# Main.net
KiCad netlist of a schematic drawn in Altium Designer
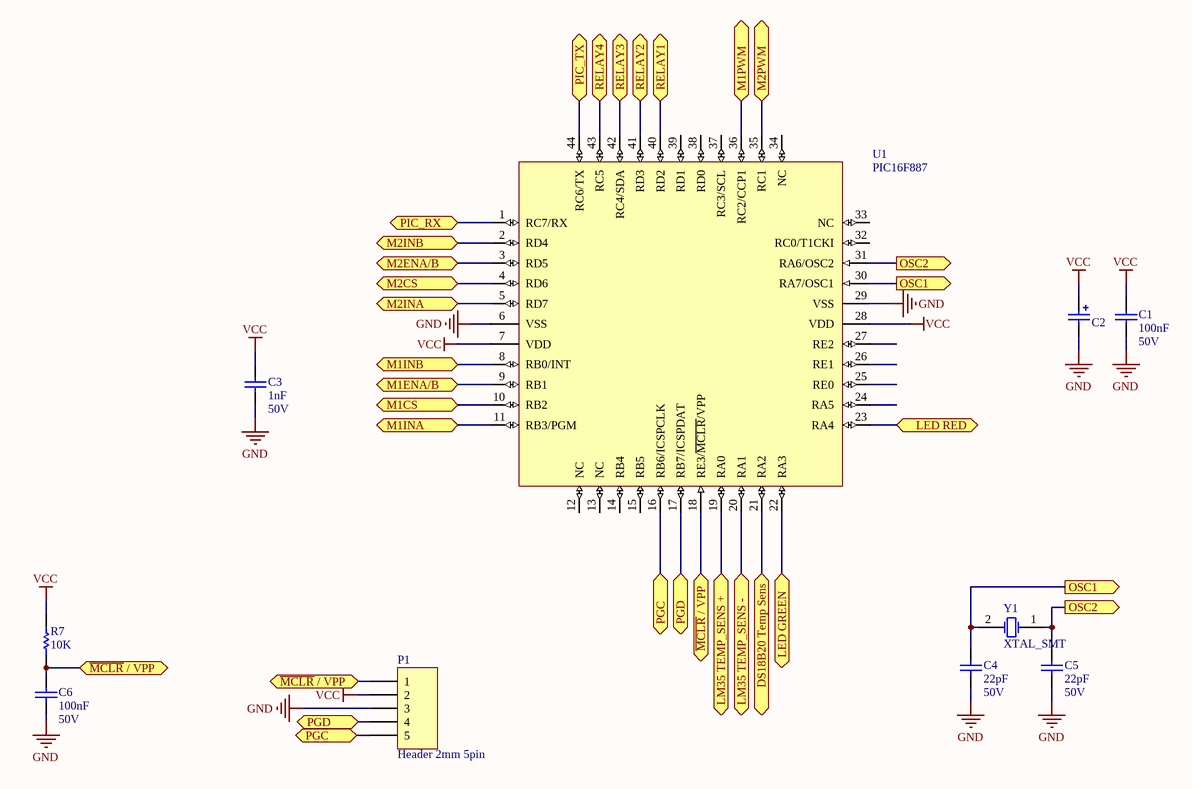
[diagram p0: Main.SchDoc]

(export (version "E")
  (design (tool "Eeschema 10.0.6"))
  (components
    (comp (ref "C1")
      (value "100nF")
      (footprint "3-0603_L")
      (description "Capacitor")
      (fields
        (field (name "VOLTAGE") "50V")
        (field (name "Comment") "Cap")
        (field (name "PUBLISHER") "Altium Limited")
      )
      (libsource (lib "Erdem_05112012") (part "Cap"))
    )
    (comp (ref "C2")
      (value "CAP-Tantal")
      (footprint "3528")
      (fields (field (name "VOLTAGE") "10V") (field (name "PUBLISHER") "Altium Limited"))
      (libsource (lib "Erdem_05112012") (part "CAP-Tantal"))
    )
    (comp (ref "C3")
      (value "1nF")
      (footprint "3-0603_L")
      (description "Capacitor")
      (fields
        (field (name "VOLTAGE") "50V")
        (field (name "Comment") "Cap")
        (field (name "PUBLISHER") "Altium Limited")
      )
      (libsource (lib "Erdem_05112012") (part "Cap"))
    )
    (comp (ref "C4")
      (value "22pF")
      (footprint "3-0603_L")
      (description "Capacitor")
      (fields
        (field (name "VOLTAGE") "50V")
        (field (name "Comment") "Cap")
        (field (name "PUBLISHER") "Altium Limited")
      )
      (libsource (lib "Erdem_05112012") (part "Cap"))
    )
    (comp (ref "C5")
      (value "22pF")
      (footprint "3-0603_L")
      (description "Capacitor")
      (fields
        (field (name "VOLTAGE") "50V")
        (field (name "Comment") "Cap")
        (field (name "PUBLISHER") "Altium Limited")
      )
      (libsource (lib "Erdem_05112012") (part "Cap"))
    )
    (comp (ref "C6")
      (value "100nF")
      (footprint "3-0603_L")
      (description "Capacitor")
      (fields
        (field (name "VOLTAGE") "50V")
        (field (name "Comment") "Cap")
        (field (name "PUBLISHER") "Altium Limited")
      )
      (libsource (lib "Erdem_05112012") (part "Cap"))
    )
    (comp (ref "P1")
      (value "Header 2mm 5pin")
      (footprint "Header 2mm 5Pin")
      (description "Header 2mm , 5-Pin")
      (fields (field (name "PUBLISHER") "Altium Limited"))
      (libsource (lib "Erdem_05112012") (part "Header 2mm 5pin"))
    )
    (comp (ref "R7")
      (value "10K")
      (footprint "3-0603_L")
      (description "Resistor")
      (fields (field (name "Comment") "Res1") (field (name "PUBLISHER") "Altium Limited"))
      (libsource (lib "Erdem_05112012") (part "Res1"))
    )
    (comp (ref "U1")
      (value "PIC16F887")
      (footprint "TQFP-44")
      (description "EPROM-Based 8-Bit CMOS Microcontroller")
      (fields (field (name "PUBLISHER") "Altium Limited"))
      (libsource (lib "Erdem_05112012") (part "PIC16F887"))
    )
    (comp (ref "Y1")
      (value "XTAL_SMT")
      (footprint "XTAL - SMT")
      (description "Crystal Oscillator")
      (fields (field (name "PUBLISHER") "Altium Limited"))
      (libsource (lib "Erdem_05112012") (part "XTAL_SMT"))
    )
  )
  (nets
    (net (code "1") (name "/DS18B20 Temp Sens") (class "Default")
      (node (ref "U1") (pin "21") (pinfunction "RA2_21") (pintype "bidirectional"))
    )
    (net (code "2") (name "/LED GREEN") (class "Default")
      (node (ref "U1") (pin "22") (pinfunction "RA3_22") (pintype "bidirectional"))
    )
    (net (code "3") (name "/LED RED") (class "Default")
      (node (ref "U1") (pin "23") (pinfunction "RA4_23") (pintype "bidirectional"))
    )
    (net (code "4") (name "/LM35 TEMP_SENS +") (class "Default")
      (node (ref "U1") (pin "19") (pinfunction "RA0_19") (pintype "bidirectional"))
    )
    (net (code "5") (name "/LM35 TEMP_SENS -") (class "Default")
      (node (ref "U1") (pin "20") (pinfunction "RA1_20") (pintype "bidirectional"))
    )
    (net (code "6") (name "/M1CS") (class "Default")
      (node (ref "U1") (pin "10") (pinfunction "RB2_10") (pintype "bidirectional"))
    )
    (net (code "7") (name "/M1ENA{slash}B") (class "Default")
      (node (ref "U1") (pin "9") (pinfunction "RB1_9") (pintype "bidirectional"))
    )
    (net (code "8") (name "/M1INA") (class "Default")
      (node (ref "U1") (pin "11") (pinfunction "RB3/PGM_11") (pintype "bidirectional"))
    )
    (net (code "9") (name "/M1INB") (class "Default")
      (node (ref "U1") (pin "8") (pinfunction "RB0/INT_8") (pintype "bidirectional"))
    )
    (net (code "10") (name "/M1PWM") (class "Default")
      (node (ref "U1") (pin "36") (pinfunction "RC2/CCP1_36") (pintype "bidirectional"))
    )
    (net (code "11") (name "/M2CS") (class "Default")
      (node (ref "U1") (pin "4") (pinfunction "RD6_4") (pintype "bidirectional"))
    )
    (net (code "12") (name "/M2ENA{slash}B") (class "Default")
      (node (ref "U1") (pin "3") (pinfunction "RD5_3") (pintype "bidirectional"))
    )
    (net (code "13") (name "/M2INA") (class "Default")
      (node (ref "U1") (pin "5") (pinfunction "RD7_5") (pintype "bidirectional"))
    )
    (net (code "14") (name "/M2INB") (class "Default")
      (node (ref "U1") (pin "2") (pinfunction "RD4_2") (pintype "bidirectional"))
    )
    (net (code "15") (name "/M2PWM") (class "Default")
      (node (ref "U1") (pin "35") (pinfunction "RC1_35") (pintype "bidirectional"))
    )
    (net (code "16") (name "/OSC1") (class "Default")
      (node (ref "C4") (pin "2") (pinfunction "2_2") (pintype "passive"))
      (node (ref "U1") (pin "30") (pinfunction "RA7/OSC1_30") (pintype "input"))
      (node (ref "Y1") (pin "2") (pinfunction "OSC2_2") (pintype "passive"))
    )
    (net (code "17") (name "/OSC2") (class "Default")
      (node (ref "C5") (pin "2") (pinfunction "2_2") (pintype "passive"))
      (node (ref "U1") (pin "31") (pinfunction "RA6/OSC2_31") (pintype "input"))
      (node (ref "Y1") (pin "1") (pinfunction "OSC1_1") (pintype "passive"))
    )
    (net (code "18") (name "/PGC") (class "Default")
      (node (ref "P1") (pin "5") (pinfunction "5_5") (pintype "passive"))
      (node (ref "U1") (pin "16") (pinfunction "RB6/ICSPCLK_16") (pintype "bidirectional"))
    )
    (net (code "19") (name "/PGD") (class "Default")
      (node (ref "P1") (pin "4") (pinfunction "4_4") (pintype "passive"))
      (node (ref "U1") (pin "17") (pinfunction "RB7/ICSPDAT_17") (pintype "bidirectional"))
    )
    (net (code "20") (name "/PIC_RX") (class "Default")
      (node (ref "U1") (pin "1") (pinfunction "RC7/RX_1") (pintype "bidirectional"))
    )
    (net (code "21") (name "/PIC_TX") (class "Default")
      (node (ref "U1") (pin "44") (pinfunction "RC6/TX_44") (pintype "bidirectional"))
    )
    (net (code "22") (name "/RELAY1") (class "Default")
      (node (ref "U1") (pin "40") (pinfunction "RD2_40") (pintype "bidirectional"))
    )
    (net (code "23") (name "/RELAY2") (class "Default")
      (node (ref "U1") (pin "41") (pinfunction "RD3_41") (pintype "bidirectional"))
    )
    (net (code "24") (name "/RELAY3") (class "Default")
      (node (ref "U1") (pin "42") (pinfunction "RC4/SDA_42") (pintype "bidirectional"))
    )
    (net (code "25") (name "/RELAY4") (class "Default")
      (node (ref "U1") (pin "43") (pinfunction "RC5_43") (pintype "bidirectional"))
    )
    (net (code "26") (name "/~{MCLR} {slash} VPP") (class "Default")
      (node (ref "C6") (pin "2") (pinfunction "2_2") (pintype "passive"))
      (node (ref "P1") (pin "1") (pinfunction "1_1") (pintype "passive"))
      (node (ref "R7") (pin "1") (pinfunction "1_1") (pintype "passive"))
      (node (ref "U1") (pin "18") (pinfunction "RE3/~{MCLR}/VPP_18") (pintype "input"))
    )
    (net (code "27") (name "GND") (class "Default")
      (node (ref "C1") (pin "1") (pinfunction "1_1") (pintype "passive"))
      (node (ref "C2") (pin "2") (pinfunction "2_2") (pintype "passive"))
      (node (ref "C3") (pin "1") (pinfunction "1_1") (pintype "passive"))
      (node (ref "C4") (pin "1") (pinfunction "1_1") (pintype "passive"))
      (node (ref "C5") (pin "1") (pinfunction "1_1") (pintype "passive"))
      (node (ref "C6") (pin "1") (pinfunction "1_1") (pintype "passive"))
      (node (ref "P1") (pin "3") (pinfunction "3_3") (pintype "passive"))
      (node (ref "U1") (pin "29") (pinfunction "VSS_29") (pintype "power_in"))
      (node (ref "U1") (pin "6") (pinfunction "VSS_6") (pintype "power_in"))
    )
    (net (code "28") (name "VCC") (class "Default")
      (node (ref "C1") (pin "2") (pinfunction "2_2") (pintype "passive"))
      (node (ref "C2") (pin "1") (pinfunction "1_1") (pintype "passive"))
      (node (ref "C3") (pin "2") (pinfunction "2_2") (pintype "passive"))
      (node (ref "P1") (pin "2") (pinfunction "2_2") (pintype "passive"))
      (node (ref "R7") (pin "2") (pinfunction "2_2") (pintype "passive"))
      (node (ref "U1") (pin "28") (pinfunction "VDD_28") (pintype "power_in"))
      (node (ref "U1") (pin "7") (pinfunction "VDD_7") (pintype "power_in"))
    )
    (net (code "29") (name "unconnected-(U1-NC-Pad12)") (class "Default")
      (node (ref "U1") (pin "12") (pinfunction "NC_12") (pintype "bidirectional"))
    )
    (net (code "30") (name "unconnected-(U1-NC-Pad13)") (class "Default")
      (node (ref "U1") (pin "13") (pinfunction "NC_13") (pintype "bidirectional"))
    )
    (net (code "31") (name "unconnected-(U1-NC-Pad33)") (class "Default")
      (node (ref "U1") (pin "33") (pinfunction "NC_33") (pintype "bidirectional"))
    )
    (net (code "32") (name "unconnected-(U1-NC-Pad34)") (class "Default")
      (node (ref "U1") (pin "34") (pinfunction "NC_34") (pintype "bidirectional"))
    )
    (net (code "33") (name "unconnected-(U1-RA5-Pad24)") (class "Default")
      (node (ref "U1") (pin "24") (pinfunction "RA5_24") (pintype "bidirectional"))
    )
    (net (code "34") (name "unconnected-(U1-RB4-Pad14)") (class "Default")
      (node (ref "U1") (pin "14") (pinfunction "RB4_14") (pintype "bidirectional"))
    )
    (net (code "35") (name "unconnected-(U1-RB5-Pad15)") (class "Default")
      (node (ref "U1") (pin "15") (pinfunction "RB5_15") (pintype "bidirectional"))
    )
    (net (code "36") (name "unconnected-(U1-RC0{slash}T1CKI-Pad32)") (class "Default")
      (node (ref "U1") (pin "32") (pinfunction "RC0/T1CKI_32") (pintype "bidirectional"))
    )
    (net (code "37") (name "unconnected-(U1-RC3{slash}SCL-Pad37)") (class "Default")
      (node (ref "U1") (pin "37") (pinfunction "RC3/SCL_37") (pintype "bidirectional"))
    )
    (net (code "38") (name "unconnected-(U1-RD0-Pad38)") (class "Default")
      (node (ref "U1") (pin "38") (pinfunction "RD0_38") (pintype "bidirectional"))
    )
    (net (code "39") (name "unconnected-(U1-RD1-Pad39)") (class "Default")
      (node (ref "U1") (pin "39") (pinfunction "RD1_39") (pintype "bidirectional"))
    )
    (net (code "40") (name "unconnected-(U1-RE0-Pad25)") (class "Default")
      (node (ref "U1") (pin "25") (pinfunction "RE0_25") (pintype "bidirectional"))
    )
    (net (code "41") (name "unconnected-(U1-RE1-Pad26)") (class "Default")
      (node (ref "U1") (pin "26") (pinfunction "RE1_26") (pintype "bidirectional"))
    )
    (net (code "42") (name "unconnected-(U1-RE2-Pad27)") (class "Default")
      (node (ref "U1") (pin "27") (pinfunction "RE2_27") (pintype "bidirectional"))
    )
  )
)
